# esp32.net
KiCad netlist of a schematic drawn in EAGLE
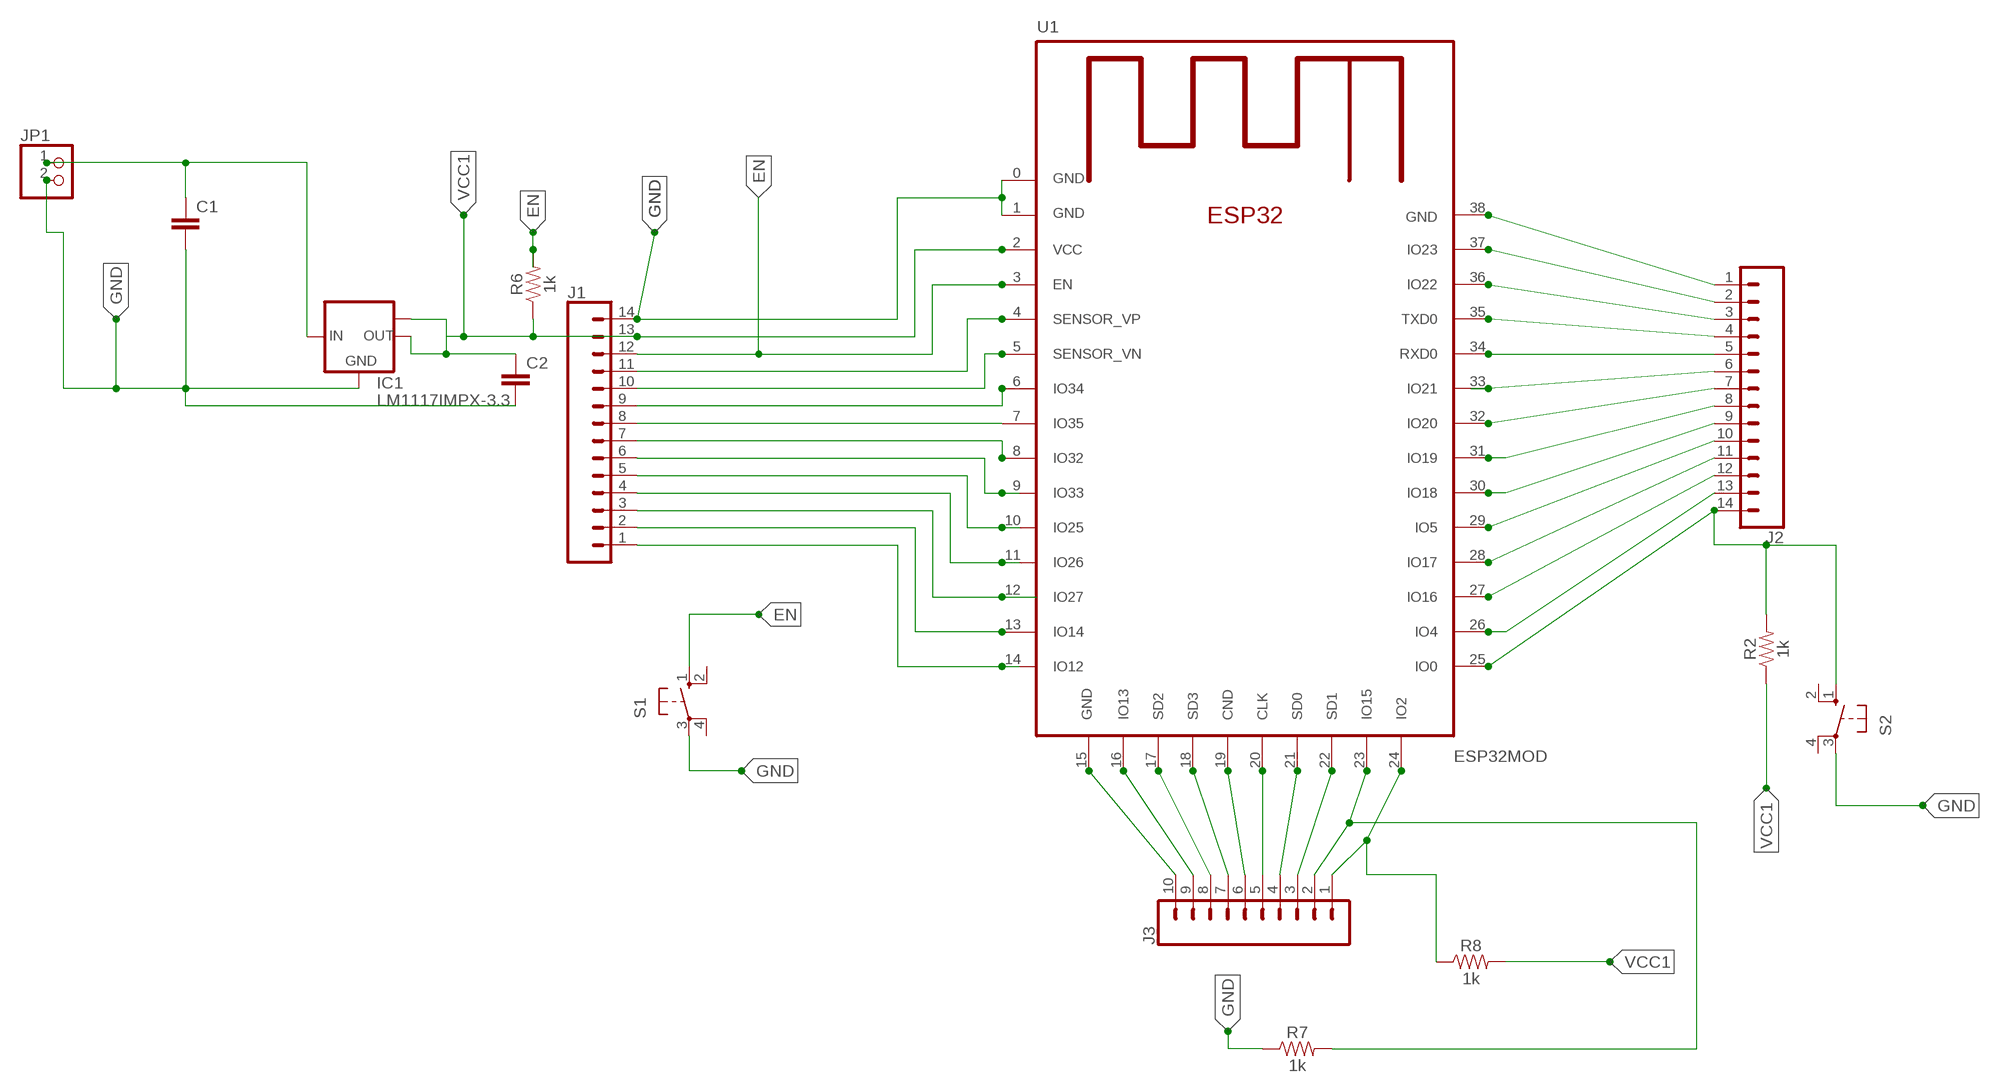
[diagram p0: schematic, sheet 1]

(export (version "E")
  (design (tool "Eeschema 10.0.6"))
  (components
    (comp (ref "C1")
      (value "C-EU025-050X050")
      (footprint "eagle-import:C025-050X050")
      (libsource (lib "eagle-import") (part "C-EU025-050X050"))
    )
    (comp (ref "C2")
      (value "C-EU025-050X050")
      (footprint "eagle-import:C025-050X050")
      (libsource (lib "eagle-import") (part "C-EU025-050X050"))
    )
    (comp (ref "IC1")
      (value "LM1117IMPX-3.3")
      (footprint "eagle-import:SOT223")
      (libsource (lib "eagle-import") (part "LM1117IMPX-3.3"))
    )
    (comp (ref "J1")
      (value "CONN_14LONGPADS")
      (footprint "eagle-import:1X14-LONGPADS")
      (libsource (lib "eagle-import") (part "CONN_14LONGPADS"))
    )
    (comp (ref "J2")
      (value "CONN_14LONGPADS")
      (footprint "eagle-import:1X14-LONGPADS")
      (libsource (lib "eagle-import") (part "CONN_14LONGPADS"))
    )
    (comp (ref "J3")
      (value "CONN_10\"")
      (footprint "eagle-import:1X10")
      (libsource (lib "eagle-import") (part "CONN_10{dblquote}"))
    )
    (comp (ref "JP1")
      (value "PINHD-1X2")
      (footprint "eagle-import:1X02")
      (libsource (lib "eagle-import") (part "PINHD-1X2"))
    )
    (comp (ref "R2")
      (value "1k")
      (footprint "eagle-import:AXIAL-0.3")
      (libsource (lib "eagle-import") (part "1KOHM-HORIZ-1/4W-1%"))
    )
    (comp (ref "R6")
      (value "1k")
      (footprint "eagle-import:AXIAL-0.3")
      (libsource (lib "eagle-import") (part "1KOHM-HORIZ-1/4W-1%"))
    )
    (comp (ref "R7")
      (value "1k")
      (footprint "eagle-import:AXIAL-0.3")
      (libsource (lib "eagle-import") (part "1KOHM-HORIZ-1/4W-1%"))
    )
    (comp (ref "R8")
      (value "1k")
      (footprint "eagle-import:AXIAL-0.3")
      (libsource (lib "eagle-import") (part "1KOHM-HORIZ-1/4W-1%"))
    )
    (comp (ref "S1")
      (value "10-XX")
      (footprint "eagle-import:B3F-10XX")
      (fields (field (name "MPN") "B3F-1000"))
      (libsource (lib "eagle-import") (part "10-XX"))
    )
    (comp (ref "S2")
      (value "10-XX")
      (footprint "eagle-import:B3F-10XX")
      (fields (field (name "MPN") "B3F-1000"))
      (libsource (lib "eagle-import") (part "10-XX"))
    )
    (comp (ref "U1")
      (value "ESP32MOD")
      (footprint "eagle-import:ESP32MOD")
      (libsource (lib "eagle-import") (part "ESP32MOD"))
    )
  )
  (nets
    (net (code "1") (name "EN") (class "Default")
      (node (ref "J1") (pin "12") (pinfunction "12_12") (pintype "passive"))
      (node (ref "R6") (pin "P$2") (pinfunction "2_P$2") (pintype "passive"))
      (node (ref "S1") (pin "1") (pinfunction "S_1") (pintype "passive"))
      (node (ref "U1") (pin "3") (pinfunction "EN_3") (pintype "bidirectional"))
    )
    (net (code "2") (name "GND") (class "Default")
      (node (ref "C1") (pin "2") (pinfunction "2_2") (pintype "passive"))
      (node (ref "C2") (pin "2") (pinfunction "2_2") (pintype "passive"))
      (node (ref "IC1") (pin "1") (pinfunction "GND_1") (pintype "input"))
      (node (ref "J1") (pin "14") (pinfunction "14_14") (pintype "passive"))
      (node (ref "J2") (pin "1") (pinfunction "1_1") (pintype "passive"))
      (node (ref "J3") (pin "10") (pinfunction "10_10") (pintype "passive"))
      (node (ref "JP1") (pin "2") (pinfunction "2_2") (pintype "passive"))
      (node (ref "R7") (pin "P$1") (pinfunction "1_P$1") (pintype "passive"))
      (node (ref "S1") (pin "3") (pinfunction "P_3") (pintype "passive"))
      (node (ref "S2") (pin "3") (pinfunction "P_3") (pintype "passive"))
      (node (ref "U1") (pin "0") (pinfunction "GND_0") (pintype "power_in"))
      (node (ref "U1") (pin "1") (pinfunction "GND_1") (pintype "power_in"))
      (node (ref "U1") (pin "15") (pinfunction "GND_15") (pintype "power_in"))
      (node (ref "U1") (pin "38") (pinfunction "GND_38") (pintype "power_in"))
    )
    (net (code "3") (name "Net-(IC1-IN)") (class "Default")
      (node (ref "C1") (pin "1") (pinfunction "1_1") (pintype "passive"))
      (node (ref "IC1") (pin "3") (pinfunction "IN_3") (pintype "input"))
      (node (ref "JP1") (pin "1") (pinfunction "1_1") (pintype "passive"))
    )
    (net (code "4") (name "Net-(R2-2)") (class "Default")
      (node (ref "J2") (pin "14") (pinfunction "14_14") (pintype "passive"))
      (node (ref "R2") (pin "P$2") (pinfunction "2_P$2") (pintype "passive"))
      (node (ref "S2") (pin "1") (pinfunction "S_1") (pintype "passive"))
      (node (ref "U1") (pin "25") (pinfunction "IO0_25") (pintype "bidirectional"))
    )
    (net (code "5") (name "Net-(R7-2)") (class "Default")
      (node (ref "J3") (pin "2") (pinfunction "2_2") (pintype "passive"))
      (node (ref "R7") (pin "P$2") (pinfunction "2_P$2") (pintype "passive"))
      (node (ref "U1") (pin "23") (pinfunction "IO15_23") (pintype "bidirectional"))
    )
    (net (code "6") (name "Net-(R8-1)") (class "Default")
      (node (ref "J3") (pin "1") (pinfunction "1_1") (pintype "passive"))
      (node (ref "R8") (pin "P$1") (pinfunction "1_P$1") (pintype "passive"))
      (node (ref "U1") (pin "24") (pinfunction "IO2_24") (pintype "bidirectional"))
    )
    (net (code "7") (name "Net-(U1-CLK)") (class "Default")
      (node (ref "J3") (pin "5") (pinfunction "5_5") (pintype "passive"))
      (node (ref "U1") (pin "20") (pinfunction "CLK_20") (pintype "bidirectional"))
    )
    (net (code "8") (name "Net-(U1-CND)") (class "Default")
      (node (ref "J3") (pin "6") (pinfunction "6_6") (pintype "passive"))
      (node (ref "U1") (pin "19") (pinfunction "CND_19") (pintype "bidirectional"))
    )
    (net (code "9") (name "Net-(U1-IO4)") (class "Default")
      (node (ref "J2") (pin "13") (pinfunction "13_13") (pintype "passive"))
      (node (ref "U1") (pin "26") (pinfunction "IO4_26") (pintype "bidirectional"))
    )
    (net (code "10") (name "Net-(U1-IO5)") (class "Default")
      (node (ref "J2") (pin "10") (pinfunction "10_10") (pintype "passive"))
      (node (ref "U1") (pin "29") (pinfunction "IO5_29") (pintype "bidirectional"))
    )
    (net (code "11") (name "Net-(U1-IO12)") (class "Default")
      (node (ref "J1") (pin "1") (pinfunction "1_1") (pintype "passive"))
      (node (ref "U1") (pin "14") (pinfunction "IO12_14") (pintype "bidirectional"))
    )
    (net (code "12") (name "Net-(U1-IO13)") (class "Default")
      (node (ref "J3") (pin "9") (pinfunction "9_9") (pintype "passive"))
      (node (ref "U1") (pin "16") (pinfunction "IO13_16") (pintype "bidirectional"))
    )
    (net (code "13") (name "Net-(U1-IO14)") (class "Default")
      (node (ref "J1") (pin "2") (pinfunction "2_2") (pintype "passive"))
      (node (ref "U1") (pin "13") (pinfunction "IO14_13") (pintype "bidirectional"))
    )
    (net (code "14") (name "Net-(U1-IO16)") (class "Default")
      (node (ref "J2") (pin "12") (pinfunction "12_12") (pintype "passive"))
      (node (ref "U1") (pin "27") (pinfunction "IO16_27") (pintype "bidirectional"))
    )
    (net (code "15") (name "Net-(U1-IO17)") (class "Default")
      (node (ref "J2") (pin "11") (pinfunction "11_11") (pintype "passive"))
      (node (ref "U1") (pin "28") (pinfunction "IO17_28") (pintype "bidirectional"))
    )
    (net (code "16") (name "Net-(U1-IO18)") (class "Default")
      (node (ref "J2") (pin "9") (pinfunction "9_9") (pintype "passive"))
      (node (ref "U1") (pin "30") (pinfunction "IO18_30") (pintype "bidirectional"))
    )
    (net (code "17") (name "Net-(U1-IO19)") (class "Default")
      (node (ref "J2") (pin "8") (pinfunction "8_8") (pintype "passive"))
      (node (ref "U1") (pin "31") (pinfunction "IO19_31") (pintype "bidirectional"))
    )
    (net (code "18") (name "Net-(U1-IO20)") (class "Default")
      (node (ref "J2") (pin "7") (pinfunction "7_7") (pintype "passive"))
      (node (ref "U1") (pin "32") (pinfunction "IO20_32") (pintype "bidirectional"))
    )
    (net (code "19") (name "Net-(U1-IO21)") (class "Default")
      (node (ref "J2") (pin "6") (pinfunction "6_6") (pintype "passive"))
      (node (ref "U1") (pin "33") (pinfunction "IO21_33") (pintype "bidirectional"))
    )
    (net (code "20") (name "Net-(U1-IO22)") (class "Default")
      (node (ref "J2") (pin "3") (pinfunction "3_3") (pintype "passive"))
      (node (ref "U1") (pin "36") (pinfunction "IO22_36") (pintype "bidirectional"))
    )
    (net (code "21") (name "Net-(U1-IO23)") (class "Default")
      (node (ref "J2") (pin "2") (pinfunction "2_2") (pintype "passive"))
      (node (ref "U1") (pin "37") (pinfunction "IO23_37") (pintype "bidirectional"))
    )
    (net (code "22") (name "Net-(U1-IO25)") (class "Default")
      (node (ref "J1") (pin "5") (pinfunction "5_5") (pintype "passive"))
      (node (ref "U1") (pin "10") (pinfunction "IO25_10") (pintype "bidirectional"))
    )
    (net (code "23") (name "Net-(U1-IO26)") (class "Default")
      (node (ref "J1") (pin "4") (pinfunction "4_4") (pintype "passive"))
      (node (ref "U1") (pin "11") (pinfunction "IO26_11") (pintype "bidirectional"))
    )
    (net (code "24") (name "Net-(U1-IO27)") (class "Default")
      (node (ref "J1") (pin "3") (pinfunction "3_3") (pintype "passive"))
      (node (ref "U1") (pin "12") (pinfunction "IO27_12") (pintype "bidirectional"))
    )
    (net (code "25") (name "Net-(U1-IO32)") (class "Default")
      (node (ref "J1") (pin "7") (pinfunction "7_7") (pintype "passive"))
      (node (ref "U1") (pin "8") (pinfunction "IO32_8") (pintype "bidirectional"))
    )
    (net (code "26") (name "Net-(U1-IO33)") (class "Default")
      (node (ref "J1") (pin "6") (pinfunction "6_6") (pintype "passive"))
      (node (ref "U1") (pin "9") (pinfunction "IO33_9") (pintype "bidirectional"))
    )
    (net (code "27") (name "Net-(U1-IO34)") (class "Default")
      (node (ref "J1") (pin "9") (pinfunction "9_9") (pintype "passive"))
      (node (ref "U1") (pin "6") (pinfunction "IO34_6") (pintype "bidirectional"))
    )
    (net (code "28") (name "Net-(U1-IO35)") (class "Default")
      (node (ref "J1") (pin "8") (pinfunction "8_8") (pintype "passive"))
      (node (ref "U1") (pin "7") (pinfunction "IO35_7") (pintype "bidirectional"))
    )
    (net (code "29") (name "Net-(U1-RXD0)") (class "Default")
      (node (ref "J2") (pin "5") (pinfunction "5_5") (pintype "passive"))
      (node (ref "U1") (pin "34") (pinfunction "RXD0_34") (pintype "bidirectional"))
    )
    (net (code "30") (name "Net-(U1-SD0)") (class "Default")
      (node (ref "J3") (pin "4") (pinfunction "4_4") (pintype "passive"))
      (node (ref "U1") (pin "21") (pinfunction "SD0_21") (pintype "bidirectional"))
    )
    (net (code "31") (name "Net-(U1-SD1)") (class "Default")
      (node (ref "J3") (pin "3") (pinfunction "3_3") (pintype "passive"))
      (node (ref "U1") (pin "22") (pinfunction "SD1_22") (pintype "bidirectional"))
    )
    (net (code "32") (name "Net-(U1-SD2)") (class "Default")
      (node (ref "J3") (pin "8") (pinfunction "8_8") (pintype "passive"))
      (node (ref "U1") (pin "17") (pinfunction "SD2_17") (pintype "bidirectional"))
    )
    (net (code "33") (name "Net-(U1-SD3)") (class "Default")
      (node (ref "J3") (pin "7") (pinfunction "7_7") (pintype "passive"))
      (node (ref "U1") (pin "18") (pinfunction "SD3_18") (pintype "bidirectional"))
    )
    (net (code "34") (name "Net-(U1-SENSOR_VN)") (class "Default")
      (node (ref "J1") (pin "10") (pinfunction "10_10") (pintype "passive"))
      (node (ref "U1") (pin "5") (pinfunction "SENSOR_VN_5") (pintype "bidirectional"))
    )
    (net (code "35") (name "Net-(U1-SENSOR_VP)") (class "Default")
      (node (ref "J1") (pin "11") (pinfunction "11_11") (pintype "passive"))
      (node (ref "U1") (pin "4") (pinfunction "SENSOR_VP_4") (pintype "bidirectional"))
    )
    (net (code "36") (name "Net-(U1-TXD0)") (class "Default")
      (node (ref "J2") (pin "4") (pinfunction "4_4") (pintype "passive"))
      (node (ref "U1") (pin "35") (pinfunction "TXD0_35") (pintype "bidirectional"))
    )
    (net (code "37") (name "VCC1") (class "Default")
      (node (ref "C2") (pin "1") (pinfunction "1_1") (pintype "passive"))
      (node (ref "IC1") (pin "2") (pinfunction "OUT_2") (pintype "passive"))
      (node (ref "IC1") (pin "TAB") (pinfunction "OUT1_TAB") (pintype "passive"))
      (node (ref "J1") (pin "13") (pinfunction "13_13") (pintype "passive"))
      (node (ref "R2") (pin "P$1") (pinfunction "1_P$1") (pintype "passive"))
      (node (ref "R6") (pin "P$1") (pinfunction "1_P$1") (pintype "passive"))
      (node (ref "R8") (pin "P$2") (pinfunction "2_P$2") (pintype "passive"))
      (node (ref "U1") (pin "2") (pinfunction "VCC_2") (pintype "power_in"))
    )
    (net (code "38") (name "unconnected-(S1-P1-Pad4)") (class "Default")
      (node (ref "S1") (pin "4") (pinfunction "P1_4") (pintype "passive"))
    )
    (net (code "39") (name "unconnected-(S1-S1-Pad2)") (class "Default")
      (node (ref "S1") (pin "2") (pinfunction "S1_2") (pintype "passive"))
    )
    (net (code "40") (name "unconnected-(S2-P1-Pad4)") (class "Default")
      (node (ref "S2") (pin "4") (pinfunction "P1_4") (pintype "passive"))
    )
    (net (code "41") (name "unconnected-(S2-S1-Pad2)") (class "Default")
      (node (ref "S2") (pin "2") (pinfunction "S1_2") (pintype "passive"))
    )
  )
)
